# 06_-Headers.net
KiCad netlist of a schematic drawn in Altium Designer
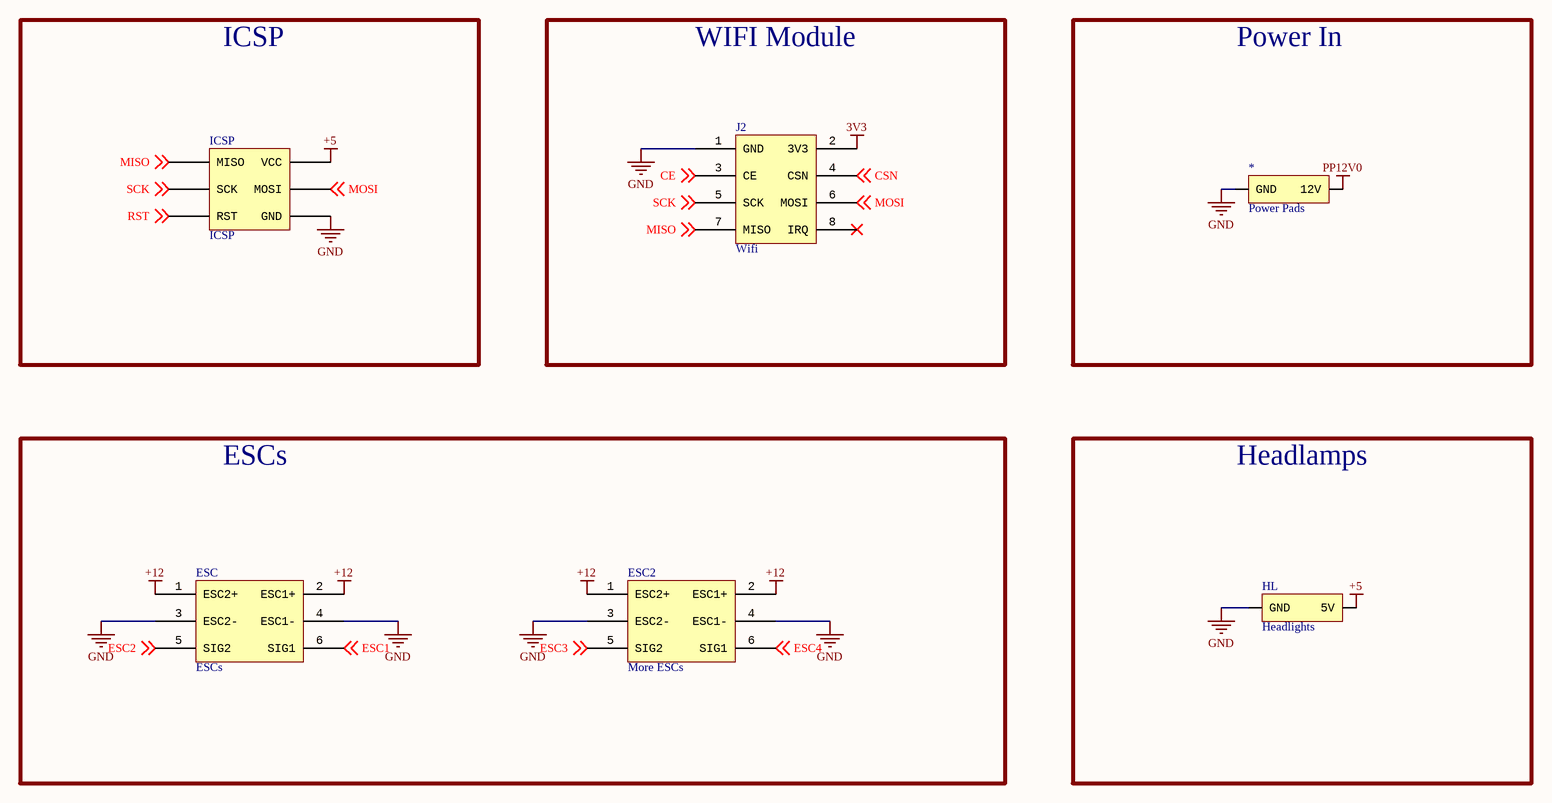
[diagram p0: [06]-Headers.SchDoc]

(export (version "E")
  (design (tool "Eeschema 10.0.6"))
  (components
    (comp (ref "*")
      (value "Power Pads")
      (footprint "Power_Switch")
      (libsource (lib "Car_PCB") (part "Power Pads"))
    )
    (comp (ref "ESC") (value "ESCs") (footprint "ESC Pads") (libsource (lib "Car_PCB") (part "ESCs")))
    (comp (ref "ESC2") (value "More ESCs") (footprint "ESC Pads") (libsource (lib "Car_PCB") (part "ESCs")))
    (comp (ref "HL")
      (value "Headlights")
      (footprint "Headlamps")
      (libsource (lib "Car_PCB") (part "Headlights"))
    )
    (comp (ref "ICSP") (value "ICSP") (footprint "ICSP") (libsource (lib "Car_PCB") (part "ICSP")))
    (comp (ref "J2") (value "Wifi") (footprint "Wifi") (libsource (lib "Car_PCB") (part "Wifi")))
  )
  (nets
    (net (code "1") (name "+5") (class "Default")
      (node (ref "HL") (pin "2") (pinfunction "5V_2") (pintype "passive"))
      (node (ref "ICSP") (pin "1") (pinfunction "VCC_1") (pintype "passive"))
    )
    (net (code "2") (name "+12") (class "Default")
      (node (ref "ESC") (pin "1") (pinfunction "ESC2+_1") (pintype "passive"))
      (node (ref "ESC") (pin "2") (pinfunction "ESC1+_2") (pintype "passive"))
      (node (ref "ESC2") (pin "1") (pinfunction "ESC2+_1") (pintype "passive"))
      (node (ref "ESC2") (pin "2") (pinfunction "ESC1+_2") (pintype "passive"))
    )
    (net (code "3") (name "3V3") (class "Default")
      (node (ref "J2") (pin "2") (pinfunction "3V3_2") (pintype "passive"))
    )
    (net (code "4") (name "CE") (class "Default")
      (node (ref "J2") (pin "3") (pinfunction "CE_3") (pintype "passive"))
    )
    (net (code "5") (name "CSN") (class "Default")
      (node (ref "J2") (pin "4") (pinfunction "CSN_4") (pintype "passive"))
    )
    (net (code "6") (name "ESC1") (class "Default")
      (node (ref "ESC") (pin "6") (pinfunction "SIG1_6") (pintype "passive"))
    )
    (net (code "7") (name "ESC2") (class "Default")
      (node (ref "ESC") (pin "5") (pinfunction "SIG2_5") (pintype "passive"))
    )
    (net (code "8") (name "ESC3") (class "Default")
      (node (ref "ESC2") (pin "5") (pinfunction "SIG2_5") (pintype "passive"))
    )
    (net (code "9") (name "ESC4") (class "Default")
      (node (ref "ESC2") (pin "6") (pinfunction "SIG1_6") (pintype "passive"))
    )
    (net (code "10") (name "GND") (class "Default")
      (node (ref "*") (pin "1") (pinfunction "GND_1") (pintype "passive"))
      (node (ref "ESC") (pin "3") (pinfunction "ESC2-_3") (pintype "passive"))
      (node (ref "ESC") (pin "4") (pinfunction "ESC1-_4") (pintype "passive"))
      (node (ref "ESC2") (pin "3") (pinfunction "ESC2-_3") (pintype "passive"))
      (node (ref "ESC2") (pin "4") (pinfunction "ESC1-_4") (pintype "passive"))
      (node (ref "HL") (pin "1") (pinfunction "GND_1") (pintype "passive"))
      (node (ref "ICSP") (pin "3") (pinfunction "GND_3") (pintype "passive"))
      (node (ref "J2") (pin "1") (pinfunction "GND_1") (pintype "passive"))
    )
    (net (code "11") (name "MISO") (class "Default")
      (node (ref "ICSP") (pin "4") (pinfunction "MISO_4") (pintype "passive"))
      (node (ref "J2") (pin "7") (pinfunction "MISO_7") (pintype "passive"))
    )
    (net (code "12") (name "MOSI") (class "Default")
      (node (ref "ICSP") (pin "2") (pinfunction "MOSI_2") (pintype "passive"))
      (node (ref "J2") (pin "6") (pinfunction "MOSI_6") (pintype "passive"))
    )
    (net (code "13") (name "PP12V0") (class "Default")
      (node (ref "*") (pin "2") (pinfunction "12V_2") (pintype "passive"))
    )
    (net (code "14") (name "RST") (class "Default")
      (node (ref "ICSP") (pin "6") (pinfunction "RST_6") (pintype "passive"))
    )
    (net (code "15") (name "SCK") (class "Default")
      (node (ref "ICSP") (pin "5") (pinfunction "SCK_5") (pintype "passive"))
      (node (ref "J2") (pin "5") (pinfunction "SCK_5") (pintype "passive"))
    )
    (net (code "16") (name "unconnected-(J2-IRQ-Pad8)") (class "Default")
      (node (ref "J2") (pin "8") (pinfunction "IRQ_8") (pintype "passive+no_connect"))
    )
  )
)
